# RP2350A_Logic_Analyzer.net
KiCad netlist of a schematic drawn in EAGLE
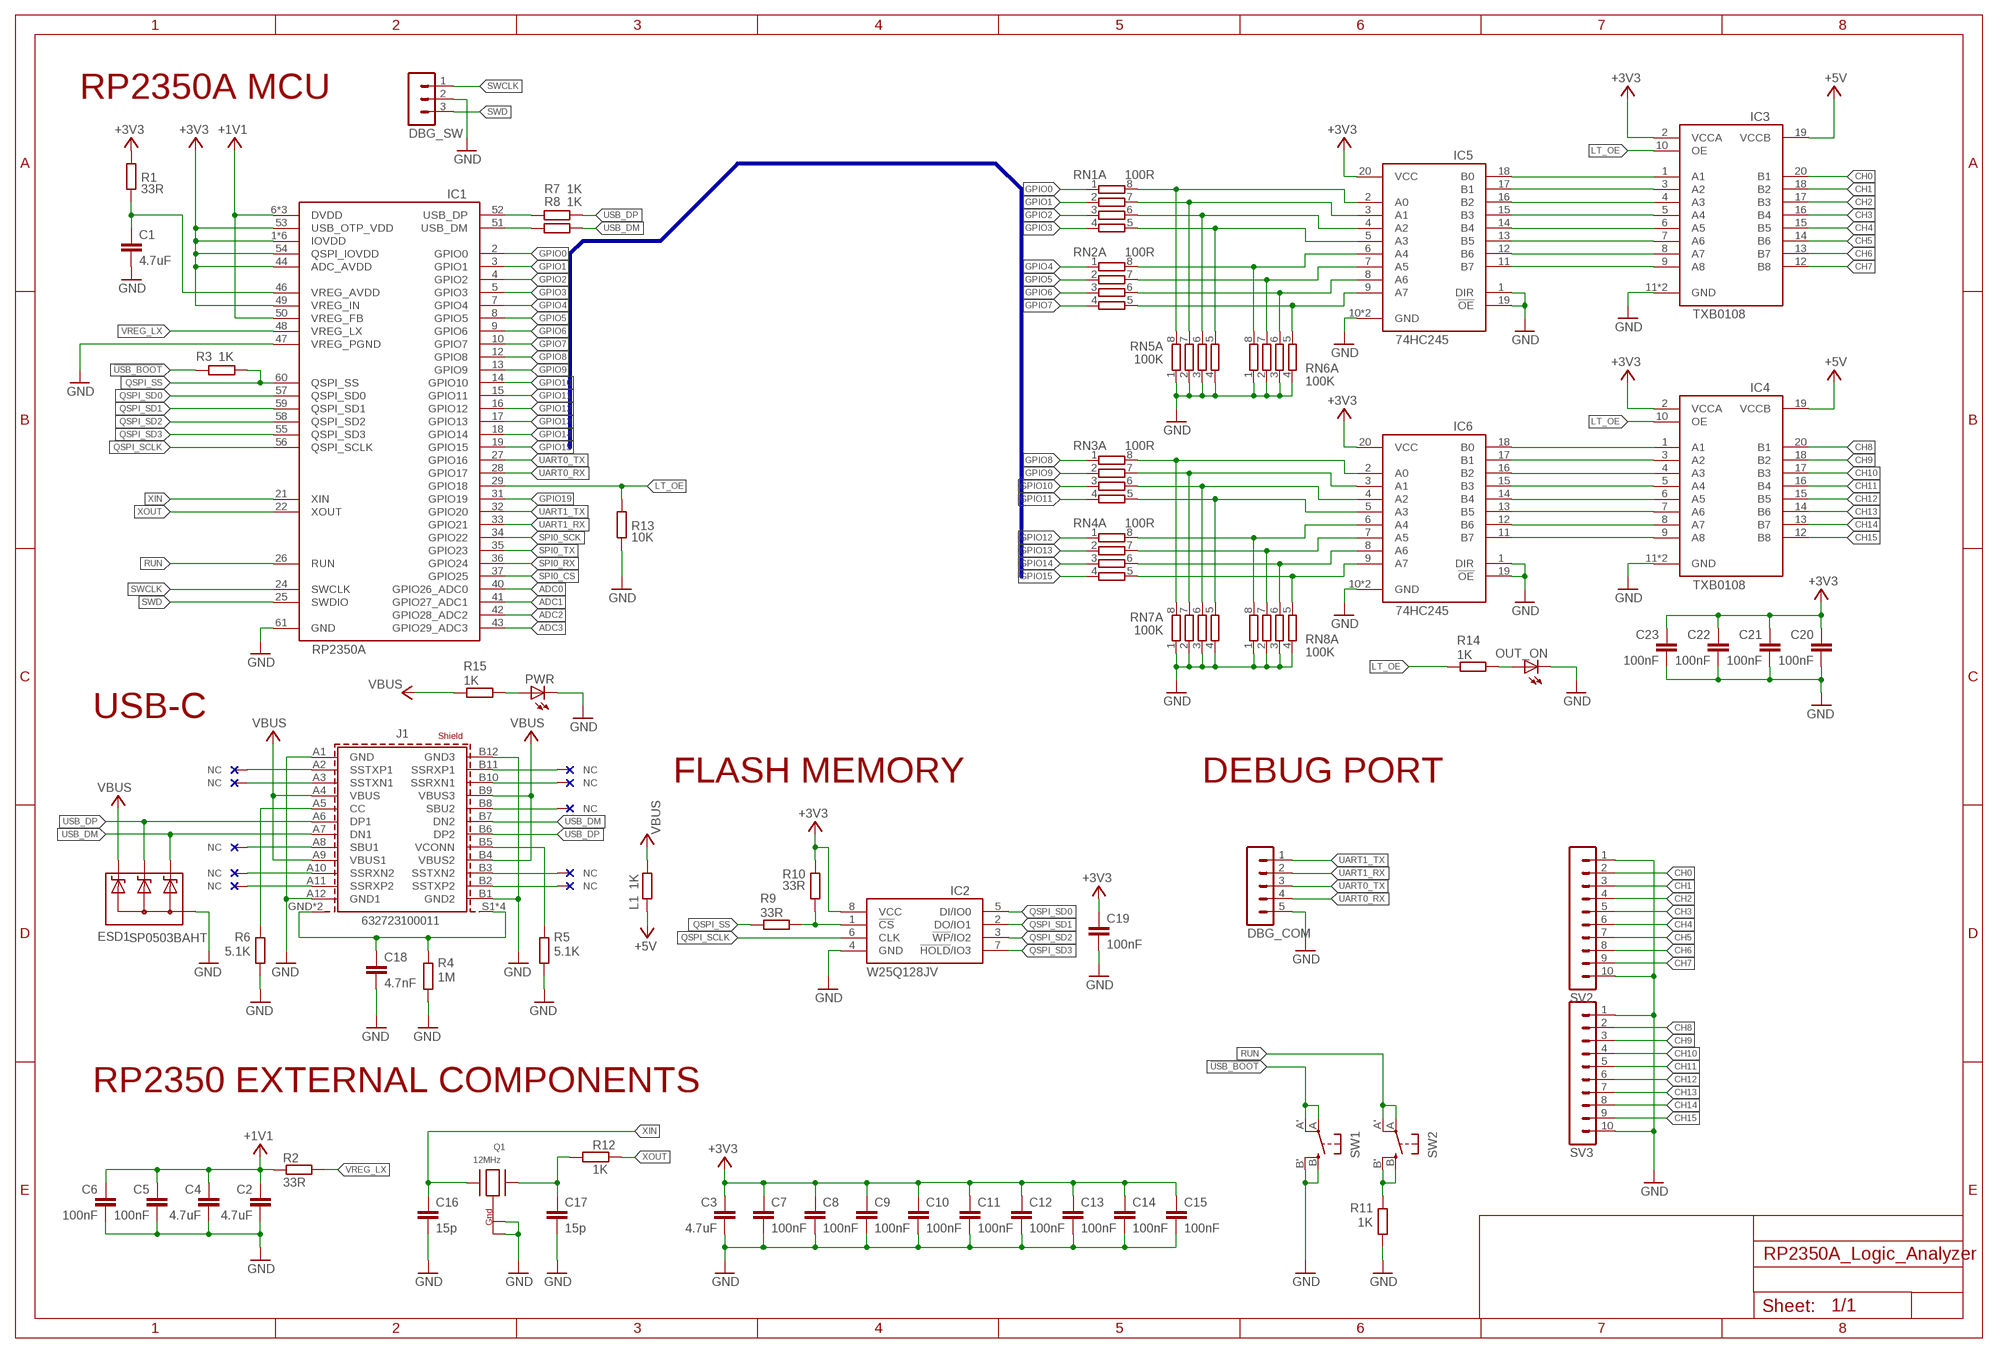
[diagram p0: schematic, sheet 1]

(export (version "E")
  (design (tool "Eeschema 10.0.6"))
  (components
    (comp (ref "C1")
      (value "4.7uF")
      (footprint "eagle-import:C0402")
      (libsource (lib "eagle-import") (part "C-EUC0402"))
    )
    (comp (ref "C2")
      (value "4.7uF")
      (footprint "eagle-import:C0402")
      (libsource (lib "eagle-import") (part "C-EUC0402"))
    )
    (comp (ref "C3")
      (value "4.7uF")
      (footprint "eagle-import:C0402")
      (libsource (lib "eagle-import") (part "C-EUC0402"))
    )
    (comp (ref "C4")
      (value "4.7uF")
      (footprint "eagle-import:C0402")
      (libsource (lib "eagle-import") (part "C-EUC0402"))
    )
    (comp (ref "C5")
      (value "100nF")
      (footprint "eagle-import:C0402")
      (libsource (lib "eagle-import") (part "C-EUC0402"))
    )
    (comp (ref "C6")
      (value "100nF")
      (footprint "eagle-import:C0402")
      (libsource (lib "eagle-import") (part "C-EUC0402"))
    )
    (comp (ref "C7")
      (value "100nF")
      (footprint "eagle-import:C0402")
      (libsource (lib "eagle-import") (part "C-EUC0402"))
    )
    (comp (ref "C8")
      (value "100nF")
      (footprint "eagle-import:C0402")
      (libsource (lib "eagle-import") (part "C-EUC0402"))
    )
    (comp (ref "C9")
      (value "100nF")
      (footprint "eagle-import:C0402")
      (libsource (lib "eagle-import") (part "C-EUC0402"))
    )
    (comp (ref "C10")
      (value "100nF")
      (footprint "eagle-import:C0402")
      (libsource (lib "eagle-import") (part "C-EUC0402"))
    )
    (comp (ref "C11")
      (value "100nF")
      (footprint "eagle-import:C0402")
      (libsource (lib "eagle-import") (part "C-EUC0402"))
    )
    (comp (ref "C12")
      (value "100nF")
      (footprint "eagle-import:C0402")
      (libsource (lib "eagle-import") (part "C-EUC0402"))
    )
    (comp (ref "C13")
      (value "100nF")
      (footprint "eagle-import:C0402")
      (libsource (lib "eagle-import") (part "C-EUC0402"))
    )
    (comp (ref "C14")
      (value "100nF")
      (footprint "eagle-import:C0402")
      (libsource (lib "eagle-import") (part "C-EUC0402"))
    )
    (comp (ref "C15")
      (value "100nF")
      (footprint "eagle-import:C0402")
      (libsource (lib "eagle-import") (part "C-EUC0402"))
    )
    (comp (ref "C16")
      (value "15p")
      (footprint "eagle-import:C0402")
      (libsource (lib "eagle-import") (part "C-EUC0402"))
    )
    (comp (ref "C17")
      (value "15p")
      (footprint "eagle-import:C0402")
      (libsource (lib "eagle-import") (part "C-EUC0402"))
    )
    (comp (ref "C18")
      (value "4.7nF")
      (footprint "eagle-import:C0402")
      (libsource (lib "eagle-import") (part "C-EUC0402"))
    )
    (comp (ref "C19")
      (value "100nF")
      (footprint "eagle-import:C0402")
      (libsource (lib "eagle-import") (part "C-EUC0402"))
    )
    (comp (ref "C20")
      (value "100nF")
      (footprint "eagle-import:C0402")
      (libsource (lib "eagle-import") (part "C-EUC0402"))
    )
    (comp (ref "C21")
      (value "100nF")
      (footprint "eagle-import:C0402")
      (libsource (lib "eagle-import") (part "C-EUC0402"))
    )
    (comp (ref "C22")
      (value "100nF")
      (footprint "eagle-import:C0402")
      (libsource (lib "eagle-import") (part "C-EUC0402"))
    )
    (comp (ref "C23")
      (value "100nF")
      (footprint "eagle-import:C0402")
      (libsource (lib "eagle-import") (part "C-EUC0402"))
    )
    (comp (ref "DBG_COM")
      (value "MA05-1")
      (footprint "eagle-import:MA05-1")
      (libsource (lib "eagle-import") (part "MA05-1"))
    )
    (comp (ref "DBG_SW")
      (value "MA03-1")
      (footprint "eagle-import:MA03-1")
      (libsource (lib "eagle-import") (part "MA03-1"))
    )
    (comp (ref "ESD1")
      (value "SP0503BAHT")
      (footprint "eagle-import:SOT143")
      (libsource (lib "eagle-import") (part "SP0503BAHT"))
    )
    (comp (ref "IC1")
      (value "RP2350AA")
      (footprint "eagle-import:QFN40P700X700X85-61T340N")
      (libsource (lib "eagle-import") (part "RP2350AA"))
    )
    (comp (ref "IC2")
      (value "W25Q128JVP")
      (footprint "eagle-import:SON127P600X500X75-8N")
      (libsource (lib "eagle-import") (part "W25Q128JVP"))
    )
    (comp (ref "IC3")
      (value "TXB0108RGY")
      (footprint "eagle-import:QFN50P350X450X100-25T200X300N")
      (libsource (lib "eagle-import") (part "TXB0108RGY"))
    )
    (comp (ref "IC4")
      (value "TXB0108RGY")
      (footprint "eagle-import:QFN50P350X450X100-25T200X300N")
      (libsource (lib "eagle-import") (part "TXB0108RGY"))
    )
    (comp (ref "IC5")
      (value "74HC245BQ")
      (footprint "eagle-import:QFN50P250X450X90-21T100X300N")
      (libsource (lib "eagle-import") (part "74HC245BQ"))
    )
    (comp (ref "IC6")
      (value "74HC245BQ")
      (footprint "eagle-import:QFN50P250X450X90-21T100X300N")
      (libsource (lib "eagle-import") (part "74HC245BQ"))
    )
    (comp (ref "J1")
      (value "632723100011")
      (footprint "eagle-import:632723100011")
      (libsource (lib "eagle-import") (part "632723100011"))
    )
    (comp (ref "L1")
      (value "1K")
      (footprint "eagle-import:R0402")
      (libsource (lib "eagle-import") (part "R-EU_R0402"))
    )
    (comp (ref "OUT_ON")
      (value "LEDCHIPLED_0603")
      (footprint "eagle-import:CHIPLED_0603")
      (libsource (lib "eagle-import") (part "LEDCHIPLED_0603"))
    )
    (comp (ref "PWR")
      (value "LEDCHIPLED_0603")
      (footprint "eagle-import:CHIPLED_0603")
      (libsource (lib "eagle-import") (part "LEDCHIPLED_0603"))
    )
    (comp (ref "Q1")
      (value "12MHz")
      (footprint "eagle-import:NX3225")
      (libsource (lib "eagle-import") (part "XTAL-4-3225"))
    )
    (comp (ref "R1")
      (value "33R")
      (footprint "eagle-import:R0402")
      (libsource (lib "eagle-import") (part "R-EU_R0402"))
    )
    (comp (ref "R2")
      (value "33R")
      (footprint "eagle-import:R0402")
      (libsource (lib "eagle-import") (part "R-EU_R0402"))
    )
    (comp (ref "R3")
      (value "1K")
      (footprint "eagle-import:R0402")
      (libsource (lib "eagle-import") (part "R-EU_R0402"))
    )
    (comp (ref "R4")
      (value "1M")
      (footprint "eagle-import:R0402")
      (libsource (lib "eagle-import") (part "R-EU_R0402"))
    )
    (comp (ref "R5")
      (value "5.1K")
      (footprint "eagle-import:R0402")
      (libsource (lib "eagle-import") (part "R-EU_R0402"))
    )
    (comp (ref "R6")
      (value "5.1K")
      (footprint "eagle-import:R0402")
      (libsource (lib "eagle-import") (part "R-EU_R0402"))
    )
    (comp (ref "R7")
      (value "1K")
      (footprint "eagle-import:R0402")
      (libsource (lib "eagle-import") (part "R-EU_R0402"))
    )
    (comp (ref "R8")
      (value "1K")
      (footprint "eagle-import:R0402")
      (libsource (lib "eagle-import") (part "R-EU_R0402"))
    )
    (comp (ref "R9")
      (value "33R")
      (footprint "eagle-import:R0402")
      (libsource (lib "eagle-import") (part "R-EU_R0402"))
    )
    (comp (ref "R10")
      (value "33R")
      (footprint "eagle-import:R0402")
      (libsource (lib "eagle-import") (part "R-EU_R0402"))
    )
    (comp (ref "R11")
      (value "1K")
      (footprint "eagle-import:R0402")
      (libsource (lib "eagle-import") (part "R-EU_R0402"))
    )
    (comp (ref "R12")
      (value "1K")
      (footprint "eagle-import:R0402")
      (libsource (lib "eagle-import") (part "R-EU_R0402"))
    )
    (comp (ref "R13")
      (value "10K")
      (footprint "eagle-import:R0402")
      (libsource (lib "eagle-import") (part "R-EU_R0402"))
    )
    (comp (ref "R14")
      (value "1K")
      (footprint "eagle-import:R0402")
      (libsource (lib "eagle-import") (part "R-EU_R0402"))
    )
    (comp (ref "R15")
      (value "1K")
      (footprint "eagle-import:R0402")
      (libsource (lib "eagle-import") (part "R-EU_R0402"))
    )
    (comp (ref "RN1")
      (value "100R")
      (footprint "eagle-import:0603-ARC")
      (libsource (lib "eagle-import") (part "4R-N0603-ARC"))
    )
    (comp (ref "RN2")
      (value "100R")
      (footprint "eagle-import:0603-ARC")
      (libsource (lib "eagle-import") (part "4R-N0603-ARC"))
    )
    (comp (ref "RN3")
      (value "100R")
      (footprint "eagle-import:0603-ARC")
      (libsource (lib "eagle-import") (part "4R-N0603-ARC"))
    )
    (comp (ref "RN4")
      (value "100R")
      (footprint "eagle-import:0603-ARC")
      (libsource (lib "eagle-import") (part "4R-N0603-ARC"))
    )
    (comp (ref "RN5")
      (value "100K")
      (footprint "eagle-import:0603-ARC")
      (libsource (lib "eagle-import") (part "4R-N0603-ARC"))
    )
    (comp (ref "RN6")
      (value "100K")
      (footprint "eagle-import:0603-ARC")
      (libsource (lib "eagle-import") (part "4R-N0603-ARC"))
    )
    (comp (ref "RN7")
      (value "100K")
      (footprint "eagle-import:0603-ARC")
      (libsource (lib "eagle-import") (part "4R-N0603-ARC"))
    )
    (comp (ref "RN8")
      (value "100K")
      (footprint "eagle-import:0603-ARC")
      (libsource (lib "eagle-import") (part "4R-N0603-ARC"))
    )
    (comp (ref "SV2")
      (value "MA10-1")
      (footprint "eagle-import:MA10-1")
      (libsource (lib "eagle-import") (part "MA10-1"))
    )
    (comp (ref "SV3")
      (value "MA10-1")
      (footprint "eagle-import:MA10-1")
      (libsource (lib "eagle-import") (part "MA10-1"))
    )
    (comp (ref "SW1")
      (value "SPST_TACT-EVQQ2")
      (footprint "eagle-import:EVQ-Q2")
      (libsource (lib "eagle-import") (part "SPST_TACT-EVQQ2"))
    )
    (comp (ref "SW2")
      (value "SPST_TACT-EVQQ2")
      (footprint "eagle-import:EVQ-Q2")
      (libsource (lib "eagle-import") (part "SPST_TACT-EVQQ2"))
    )
  )
  (nets
    (net (code "1") (name "+1V1") (class "Default")
      (node (ref "C2") (pin "1") (pinfunction "1_1") (pintype "passive"))
      (node (ref "C4") (pin "1") (pinfunction "1_1") (pintype "passive"))
      (node (ref "C5") (pin "1") (pinfunction "1_1") (pintype "passive"))
      (node (ref "C6") (pin "1") (pinfunction "1_1") (pintype "passive"))
      (node (ref "IC1") (pin "23") (pinfunction "DVDD_23") (pintype "power_in"))
      (node (ref "IC1") (pin "39") (pinfunction "DVDD_39") (pintype "power_in"))
      (node (ref "IC1") (pin "50") (pinfunction "VREG_FB_50") (pintype "power_in"))
      (node (ref "IC1") (pin "6") (pinfunction "DVDD_6") (pintype "power_in"))
      (node (ref "R2") (pin "2") (pinfunction "2_2") (pintype "passive"))
    )
    (net (code "2") (name "+3V3") (class "Default")
      (node (ref "C10") (pin "1") (pinfunction "1_1") (pintype "passive"))
      (node (ref "C11") (pin "1") (pinfunction "1_1") (pintype "passive"))
      (node (ref "C12") (pin "1") (pinfunction "1_1") (pintype "passive"))
      (node (ref "C13") (pin "1") (pinfunction "1_1") (pintype "passive"))
      (node (ref "C14") (pin "1") (pinfunction "1_1") (pintype "passive"))
      (node (ref "C15") (pin "1") (pinfunction "1_1") (pintype "passive"))
      (node (ref "C19") (pin "1") (pinfunction "1_1") (pintype "passive"))
      (node (ref "C20") (pin "1") (pinfunction "1_1") (pintype "passive"))
      (node (ref "C21") (pin "1") (pinfunction "1_1") (pintype "passive"))
      (node (ref "C22") (pin "1") (pinfunction "1_1") (pintype "passive"))
      (node (ref "C23") (pin "1") (pinfunction "1_1") (pintype "passive"))
      (node (ref "C3") (pin "1") (pinfunction "1_1") (pintype "passive"))
      (node (ref "C7") (pin "1") (pinfunction "1_1") (pintype "passive"))
      (node (ref "C8") (pin "1") (pinfunction "1_1") (pintype "passive"))
      (node (ref "C9") (pin "1") (pinfunction "1_1") (pintype "passive"))
      (node (ref "IC1") (pin "1") (pinfunction "IOVDD_1") (pintype "power_in"))
      (node (ref "IC1") (pin "11") (pinfunction "IOVDD_11") (pintype "power_in"))
      (node (ref "IC1") (pin "20") (pinfunction "IOVDD_20") (pintype "power_in"))
      (node (ref "IC1") (pin "30") (pinfunction "IOVDD_30") (pintype "power_in"))
      (node (ref "IC1") (pin "38") (pinfunction "IOVDD_38") (pintype "power_in"))
      (node (ref "IC1") (pin "44") (pinfunction "ADC_AVDD_44") (pintype "power_in"))
      (node (ref "IC1") (pin "45") (pinfunction "IOVDD_45") (pintype "power_in"))
      (node (ref "IC1") (pin "49") (pinfunction "VREG_IN_49") (pintype "power_in"))
      (node (ref "IC1") (pin "53") (pinfunction "USB_OTP_VDD_53") (pintype "bidirectional"))
      (node (ref "IC1") (pin "54") (pinfunction "QSPI_IOVDD_54") (pintype "power_in"))
      (node (ref "IC2") (pin "8") (pinfunction "VCC_8") (pintype "power_in"))
      (node (ref "IC3") (pin "2") (pinfunction "VCCA_2") (pintype "power_in"))
      (node (ref "IC4") (pin "2") (pinfunction "VCCA_2") (pintype "power_in"))
      (node (ref "IC5") (pin "20") (pinfunction "VCC_20") (pintype "power_in"))
      (node (ref "IC6") (pin "20") (pinfunction "VCC_20") (pintype "power_in"))
      (node (ref "R1") (pin "1") (pinfunction "1_1") (pintype "passive"))
      (node (ref "R10") (pin "1") (pinfunction "1_1") (pintype "passive"))
    )
    (net (code "3") (name "+5V") (class "Default")
      (node (ref "IC3") (pin "19") (pinfunction "VCCB_19") (pintype "power_in"))
      (node (ref "IC4") (pin "19") (pinfunction "VCCB_19") (pintype "power_in"))
      (node (ref "L1") (pin "1") (pinfunction "1_1") (pintype "passive"))
    )
    (net (code "4") (name "/~{USB_BOOT}") (class "Default")
      (node (ref "R3") (pin "1") (pinfunction "1_1") (pintype "passive"))
      (node (ref "SW1") (pin "A") (pinfunction "P_A") (pintype "passive"))
      (node (ref "SW1") (pin "A'") (pinfunction "P1_A'") (pintype "passive"))
    )
    (net (code "5") (name "ADC0") (class "Default")
      (node (ref "IC1") (pin "40") (pinfunction "GPIO26_ADC0_40") (pintype "bidirectional"))
    )
    (net (code "6") (name "ADC1") (class "Default")
      (node (ref "IC1") (pin "41") (pinfunction "GPIO27_ADC1_41") (pintype "bidirectional"))
    )
    (net (code "7") (name "ADC2") (class "Default")
      (node (ref "IC1") (pin "42") (pinfunction "GPIO28_ADC2_42") (pintype "bidirectional"))
    )
    (net (code "8") (name "ADC3") (class "Default")
      (node (ref "IC1") (pin "43") (pinfunction "GPIO29_ADC3_43") (pintype "bidirectional"))
    )
    (net (code "9") (name "CH0") (class "Default")
      (node (ref "IC3") (pin "20") (pinfunction "B1_20") (pintype "bidirectional"))
      (node (ref "SV2") (pin "2") (pinfunction "2_2") (pintype "passive"))
    )
    (net (code "10") (name "CH1") (class "Default")
      (node (ref "IC3") (pin "18") (pinfunction "B2_18") (pintype "bidirectional"))
      (node (ref "SV2") (pin "3") (pinfunction "3_3") (pintype "passive"))
    )
    (net (code "11") (name "CH2") (class "Default")
      (node (ref "IC3") (pin "17") (pinfunction "B3_17") (pintype "bidirectional"))
      (node (ref "SV2") (pin "4") (pinfunction "4_4") (pintype "passive"))
    )
    (net (code "12") (name "CH3") (class "Default")
      (node (ref "IC3") (pin "16") (pinfunction "B4_16") (pintype "bidirectional"))
      (node (ref "SV2") (pin "5") (pinfunction "5_5") (pintype "passive"))
    )
    (net (code "13") (name "CH4") (class "Default")
      (node (ref "IC3") (pin "15") (pinfunction "B5_15") (pintype "bidirectional"))
      (node (ref "SV2") (pin "6") (pinfunction "6_6") (pintype "passive"))
    )
    (net (code "14") (name "CH5") (class "Default")
      (node (ref "IC3") (pin "14") (pinfunction "B6_14") (pintype "bidirectional"))
      (node (ref "SV2") (pin "7") (pinfunction "7_7") (pintype "passive"))
    )
    (net (code "15") (name "CH6") (class "Default")
      (node (ref "IC3") (pin "13") (pinfunction "B7_13") (pintype "bidirectional"))
      (node (ref "SV2") (pin "8") (pinfunction "8_8") (pintype "passive"))
    )
    (net (code "16") (name "CH7") (class "Default")
      (node (ref "IC3") (pin "12") (pinfunction "B8_12") (pintype "bidirectional"))
      (node (ref "SV2") (pin "9") (pinfunction "9_9") (pintype "passive"))
    )
    (net (code "17") (name "CH8") (class "Default")
      (node (ref "IC4") (pin "20") (pinfunction "B1_20") (pintype "bidirectional"))
      (node (ref "SV3") (pin "2") (pinfunction "2_2") (pintype "passive"))
    )
    (net (code "18") (name "CH9") (class "Default")
      (node (ref "IC4") (pin "18") (pinfunction "B2_18") (pintype "bidirectional"))
      (node (ref "SV3") (pin "3") (pinfunction "3_3") (pintype "passive"))
    )
    (net (code "19") (name "CH10") (class "Default")
      (node (ref "IC4") (pin "17") (pinfunction "B3_17") (pintype "bidirectional"))
      (node (ref "SV3") (pin "4") (pinfunction "4_4") (pintype "passive"))
    )
    (net (code "20") (name "CH11") (class "Default")
      (node (ref "IC4") (pin "16") (pinfunction "B4_16") (pintype "bidirectional"))
      (node (ref "SV3") (pin "5") (pinfunction "5_5") (pintype "passive"))
    )
    (net (code "21") (name "CH12") (class "Default")
      (node (ref "IC4") (pin "15") (pinfunction "B5_15") (pintype "bidirectional"))
      (node (ref "SV3") (pin "6") (pinfunction "6_6") (pintype "passive"))
    )
    (net (code "22") (name "CH13") (class "Default")
      (node (ref "IC4") (pin "14") (pinfunction "B6_14") (pintype "bidirectional"))
      (node (ref "SV3") (pin "7") (pinfunction "7_7") (pintype "passive"))
    )
    (net (code "23") (name "CH14") (class "Default")
      (node (ref "IC4") (pin "13") (pinfunction "B7_13") (pintype "bidirectional"))
      (node (ref "SV3") (pin "8") (pinfunction "8_8") (pintype "passive"))
    )
    (net (code "24") (name "CH15") (class "Default")
      (node (ref "IC4") (pin "12") (pinfunction "B8_12") (pintype "bidirectional"))
      (node (ref "SV3") (pin "9") (pinfunction "9_9") (pintype "passive"))
    )
    (net (code "25") (name "GND") (class "Default")
      (node (ref "C1") (pin "2") (pinfunction "2_2") (pintype "passive"))
      (node (ref "C10") (pin "2") (pinfunction "2_2") (pintype "passive"))
      (node (ref "C11") (pin "2") (pinfunction "2_2") (pintype "passive"))
      (node (ref "C12") (pin "2") (pinfunction "2_2") (pintype "passive"))
      (node (ref "C13") (pin "2") (pinfunction "2_2") (pintype "passive"))
      (node (ref "C14") (pin "2") (pinfunction "2_2") (pintype "passive"))
      (node (ref "C15") (pin "2") (pinfunction "2_2") (pintype "passive"))
      (node (ref "C16") (pin "2") (pinfunction "2_2") (pintype "passive"))
      (node (ref "C17") (pin "2") (pinfunction "2_2") (pintype "passive"))
      (node (ref "C18") (pin "2") (pinfunction "2_2") (pintype "passive"))
      (node (ref "C19") (pin "2") (pinfunction "2_2") (pintype "passive"))
      (node (ref "C2") (pin "2") (pinfunction "2_2") (pintype "passive"))
      (node (ref "C20") (pin "2") (pinfunction "2_2") (pintype "passive"))
      (node (ref "C21") (pin "2") (pinfunction "2_2") (pintype "passive"))
      (node (ref "C22") (pin "2") (pinfunction "2_2") (pintype "passive"))
      (node (ref "C23") (pin "2") (pinfunction "2_2") (pintype "passive"))
      (node (ref "C3") (pin "2") (pinfunction "2_2") (pintype "passive"))
      (node (ref "C4") (pin "2") (pinfunction "2_2") (pintype "passive"))
      (node (ref "C5") (pin "2") (pinfunction "2_2") (pintype "passive"))
      (node (ref "C6") (pin "2") (pinfunction "2_2") (pintype "passive"))
      (node (ref "C7") (pin "2") (pinfunction "2_2") (pintype "passive"))
      (node (ref "C8") (pin "2") (pinfunction "2_2") (pintype "passive"))
      (node (ref "C9") (pin "2") (pinfunction "2_2") (pintype "passive"))
      (node (ref "DBG_COM") (pin "5") (pinfunction "5_5") (pintype "passive"))
      (node (ref "DBG_SW") (pin "2") (pinfunction "2_2") (pintype "passive"))
      (node (ref "ESD1") (pin "1") (pinfunction "A_1") (pintype "bidirectional"))
      (node (ref "IC1") (pin "47") (pinfunction "VREG_PGND_47") (pintype "power_in"))
      (node (ref "IC1") (pin "61") (pinfunction "GND_61") (pintype "power_in"))
      (node (ref "IC2") (pin "4") (pinfunction "GND_4") (pintype "power_in"))
      (node (ref "IC3") (pin "11") (pinfunction "GND_11") (pintype "power_in"))
      (node (ref "IC3") (pin "PAD") (pinfunction "GND_PAD") (pintype "power_in"))
      (node (ref "IC4") (pin "11") (pinfunction "GND_11") (pintype "power_in"))
      (node (ref "IC4") (pin "PAD") (pinfunction "GND_PAD") (pintype "power_in"))
      (node (ref "IC5") (pin "1") (pinfunction "DIR_1") (pintype "input"))
      (node (ref "IC5") (pin "10") (pinfunction "GND_10") (pintype "power_in"))
      (node (ref "IC5") (pin "19") (pinfunction "~{OE}_19") (pintype "input"))
      (node (ref "IC5") (pin "PAD") (pinfunction "GND_PAD") (pintype "power_in"))
      (node (ref "IC6") (pin "1") (pinfunction "DIR_1") (pintype "input"))
      (node (ref "IC6") (pin "10") (pinfunction "GND_10") (pintype "power_in"))
      (node (ref "IC6") (pin "19") (pinfunction "~{OE}_19") (pintype "input"))
      (node (ref "IC6") (pin "PAD") (pinfunction "GND_PAD") (pintype "power_in"))
      (node (ref "J1") (pin "A1") (pinfunction "GND_A1") (pintype "passive"))
      (node (ref "J1") (pin "A12") (pinfunction "GND1_A12") (pintype "passive"))
      (node (ref "J1") (pin "B1") (pinfunction "GND2_B1") (pintype "passive"))
      (node (ref "J1") (pin "B12") (pinfunction "GND3_B12") (pintype "passive"))
      (node (ref "OUT_ON") (pin "C") (pinfunction "C_C") (pintype "passive"))
      (node (ref "PWR") (pin "C") (pinfunction "C_C") (pintype "passive"))
      (node (ref "Q1") (pin "2") (pinfunction "G2_2") (pintype "power_in"))
      (node (ref "Q1") (pin "4") (pinfunction "G1_4") (pintype "power_in"))
      (node (ref "R11") (pin "1") (pinfunction "1_1") (pintype "passive"))
      (node (ref "R13") (pin "2") (pinfunction "2_2") (pintype "passive"))
      (node (ref "R4") (pin "1") (pinfunction "1_1") (pintype "passive"))
      (node (ref "R5") (pin "1") (pinfunction "1_1") (pintype "passive"))
      (node (ref "R6") (pin "1") (pinfunction "1_1") (pintype "passive"))
      (node (ref "RN5") (pin "1") (pinfunction "1_1") (pintype "passive"))
      (node (ref "RN5") (pin "2") (pinfunction "1_2") (pintype "passive"))
      (node (ref "RN5") (pin "3") (pinfunction "1_3") (pintype "passive"))
      (node (ref "RN5") (pin "4") (pinfunction "1_4") (pintype "passive"))
      (node (ref "RN6") (pin "1") (pinfunction "1_1") (pintype "passive"))
      (node (ref "RN6") (pin "2") (pinfunction "1_2") (pintype "passive"))
      (node (ref "RN6") (pin "3") (pinfunction "1_3") (pintype "passive"))
      (node (ref "RN6") (pin "4") (pinfunction "1_4") (pintype "passive"))
      (node (ref "RN7") (pin "1") (pinfunction "1_1") (pintype "passive"))
      (node (ref "RN7") (pin "2") (pinfunction "1_2") (pintype "passive"))
      (node (ref "RN7") (pin "3") (pinfunction "1_3") (pintype "passive"))
      (node (ref "RN7") (pin "4") (pinfunction "1_4") (pintype "passive"))
      (node (ref "RN8") (pin "1") (pinfunction "1_1") (pintype "passive"))
      (node (ref "RN8") (pin "2") (pinfunction "1_2") (pintype "passive"))
      (node (ref "RN8") (pin "3") (pinfunction "1_3") (pintype "passive"))
      (node (ref "RN8") (pin "4") (pinfunction "1_4") (pintype "passive"))
      (node (ref "SV2") (pin "1") (pinfunction "1_1") (pintype "passive"))
      (node (ref "SV2") (pin "10") (pinfunction "10_10") (pintype "passive"))
      (node (ref "SV3") (pin "1") (pinfunction "1_1") (pintype "passive"))
      (node (ref "SV3") (pin "10") (pinfunction "10_10") (pintype "passive"))
      (node (ref "SW1") (pin "B") (pinfunction "S_B") (pintype "passive"))
      (node (ref "SW1") (pin "B'") (pinfunction "S1_B'") (pintype "passive"))
    )
    (net (code "26") (name "GPIO0") (class "Default")
      (node (ref "IC1") (pin "2") (pinfunction "GPIO0_2") (pintype "bidirectional"))
      (node (ref "RN1") (pin "1") (pinfunction "1_1") (pintype "passive"))
    )
    (net (code "27") (name "GPIO1") (class "Default")
      (node (ref "IC1") (pin "3") (pinfunction "GPIO1_3") (pintype "bidirectional"))
      (node (ref "RN1") (pin "2") (pinfunction "1_2") (pintype "passive"))
    )
    (net (code "28") (name "GPIO2") (class "Default")
      (node (ref "IC1") (pin "4") (pinfunction "GPIO2_4") (pintype "bidirectional"))
      (node (ref "RN1") (pin "3") (pinfunction "1_3") (pintype "passive"))
    )
    (net (code "29") (name "GPIO3") (class "Default")
      (node (ref "IC1") (pin "5") (pinfunction "GPIO3_5") (pintype "bidirectional"))
      (node (ref "RN1") (pin "4") (pinfunction "1_4") (pintype "passive"))
    )
    (net (code "30") (name "GPIO4") (class "Default")
      (node (ref "IC1") (pin "7") (pinfunction "GPIO4_7") (pintype "bidirectional"))
      (node (ref "RN2") (pin "1") (pinfunction "1_1") (pintype "passive"))
    )
    (net (code "31") (name "GPIO5") (class "Default")
      (node (ref "IC1") (pin "8") (pinfunction "GPIO5_8") (pintype "bidirectional"))
      (node (ref "RN2") (pin "2") (pinfunction "1_2") (pintype "passive"))
    )
    (net (code "32") (name "GPIO6") (class "Default")
      (node (ref "IC1") (pin "9") (pinfunction "GPIO6_9") (pintype "bidirectional"))
      (node (ref "RN2") (pin "3") (pinfunction "1_3") (pintype "passive"))
    )
    (net (code "33") (name "GPIO7") (class "Default")
      (node (ref "IC1") (pin "10") (pinfunction "GPIO7_10") (pintype "bidirectional"))
      (node (ref "RN2") (pin "4") (pinfunction "1_4") (pintype "passive"))
    )
    (net (code "34") (name "GPIO8") (class "Default")
      (node (ref "IC1") (pin "12") (pinfunction "GPIO8_12") (pintype "bidirectional"))
      (node (ref "RN3") (pin "1") (pinfunction "1_1") (pintype "passive"))
    )
    (net (code "35") (name "GPIO9") (class "Default")
      (node (ref "IC1") (pin "13") (pinfunction "GPIO9_13") (pintype "bidirectional"))
      (node (ref "RN3") (pin "2") (pinfunction "1_2") (pintype "passive"))
    )
    (net (code "36") (name "GPIO10") (class "Default")
      (node (ref "IC1") (pin "14") (pinfunction "GPIO10_14") (pintype "bidirectional"))
      (node (ref "RN3") (pin "3") (pinfunction "1_3") (pintype "passive"))
    )
    (net (code "37") (name "GPIO11") (class "Default")
      (node (ref "IC1") (pin "15") (pinfunction "GPIO11_15") (pintype "bidirectional"))
      (node (ref "RN3") (pin "4") (pinfunction "1_4") (pintype "passive"))
    )
    (net (code "38") (name "GPIO12") (class "Default")
      (node (ref "IC1") (pin "16") (pinfunction "GPIO12_16") (pintype "bidirectional"))
      (node (ref "RN4") (pin "1") (pinfunction "1_1") (pintype "passive"))
    )
    (net (code "39") (name "GPIO13") (class "Default")
      (node (ref "IC1") (pin "17") (pinfunction "GPIO13_17") (pintype "bidirectional"))
      (node (ref "RN4") (pin "2") (pinfunction "1_2") (pintype "passive"))
    )
    (net (code "40") (name "GPIO14") (class "Default")
      (node (ref "IC1") (pin "18") (pinfunction "GPIO14_18") (pintype "bidirectional"))
      (node (ref "RN4") (pin "3") (pinfunction "1_3") (pintype "passive"))
    )
    (net (code "41") (name "GPIO15") (class "Default")
      (node (ref "IC1") (pin "19") (pinfunction "GPIO15_19") (pintype "bidirectional"))
      (node (ref "RN4") (pin "4") (pinfunction "1_4") (pintype "passive"))
    )
    (net (code "42") (name "GPIO19") (class "Default")
      (node (ref "IC1") (pin "31") (pinfunction "GPIO19_31") (pintype "bidirectional"))
    )
    (net (code "43") (name "LT_OE") (class "Default")
      (node (ref "IC1") (pin "29") (pinfunction "GPIO18_29") (pintype "bidirectional"))
      (node (ref "IC3") (pin "10") (pinfunction "OE_10") (pintype "input"))
      (node (ref "IC4") (pin "10") (pinfunction "OE_10") (pintype "input"))
      (node (ref "R13") (pin "1") (pinfunction "1_1") (pintype "passive"))
      (node (ref "R14") (pin "1") (pinfunction "1_1") (pintype "passive"))
    )
    (net (code "44") (name "Net-(C18-Pad1)") (class "Default")
      (node (ref "C18") (pin "1") (pinfunction "1_1") (pintype "passive"))
      (node (ref "J1") (pin "GND") (pinfunction "SHIELD_GND") (pintype "passive"))
      (node (ref "J1") (pin "GND1") (pinfunction "SHIELD_GND1") (pintype "passive"))
      (node (ref "J1") (pin "S1") (pinfunction "SHIELD1_S1") (pintype "passive"))
      (node (ref "J1") (pin "S2") (pinfunction "SHIELD1_S2") (pintype "passive"))
      (node (ref "J1") (pin "S3") (pinfunction "SHIELD1_S3") (pintype "passive"))
      (node (ref "J1") (pin "S4") (pinfunction "SHIELD1_S4") (pintype "passive"))
      (node (ref "R4") (pin "2") (pinfunction "2_2") (pintype "passive"))
    )
    (net (code "45") (name "Net-(IC1-USB_DM)") (class "Default")
      (node (ref "IC1") (pin "51") (pinfunction "USB_DM_51") (pintype "bidirectional"))
      (node (ref "R8") (pin "1") (pinfunction "1_1") (pintype "passive"))
    )
    (net (code "46") (name "Net-(IC1-USB_DP)") (class "Default")
      (node (ref "IC1") (pin "52") (pinfunction "USB_DP_52") (pintype "bidirectional"))
      (node (ref "R7") (pin "1") (pinfunction "1_1") (pintype "passive"))
    )
    (net (code "47") (name "Net-(IC1-VREG_AVDD)") (class "Default")
      (node (ref "C1") (pin "1") (pinfunction "1_1") (pintype "passive"))
      (node (ref "IC1") (pin "46") (pinfunction "VREG_AVDD_46") (pintype "power_in"))
      (node (ref "R1") (pin "2") (pinfunction "2_2") (pintype "passive"))
    )
    (net (code "48") (name "Net-(IC2-~{CS})") (class "Default")
      (node (ref "IC2") (pin "1") (pinfunction "~{CS}_1") (pintype "bidirectional"))
      (node (ref "R10") (pin "2") (pinfunction "2_2") (pintype "passive"))
      (node (ref "R9") (pin "2") (pinfunction "2_2") (pintype "passive"))
    )
    (net (code "49") (name "Net-(IC3-A1)") (class "Default")
      (node (ref "IC3") (pin "1") (pinfunction "A1_1") (pintype "bidirectional"))
      (node (ref "IC5") (pin "18") (pinfunction "B0_18") (pintype "bidirectional"))
    )
    (net (code "50") (name "Net-(IC3-A2)") (class "Default")
      (node (ref "IC3") (pin "3") (pinfunction "A2_3") (pintype "bidirectional"))
      (node (ref "IC5") (pin "17") (pinfunction "B1_17") (pintype "bidirectional"))
    )
    (net (code "51") (name "Net-(IC3-A3)") (class "Default")
      (node (ref "IC3") (pin "4") (pinfunction "A3_4") (pintype "bidirectional"))
      (node (ref "IC5") (pin "16") (pinfunction "B2_16") (pintype "bidirectional"))
    )
    (net (code "52") (name "Net-(IC3-A4)") (class "Default")
      (node (ref "IC3") (pin "5") (pinfunction "A4_5") (pintype "bidirectional"))
      (node (ref "IC5") (pin "15") (pinfunction "B3_15") (pintype "bidirectional"))
    )
    (net (code "53") (name "Net-(IC3-A5)") (class "Default")
      (node (ref "IC3") (pin "6") (pinfunction "A5_6") (pintype "bidirectional"))
      (node (ref "IC5") (pin "14") (pinfunction "B4_14") (pintype "bidirectional"))
    )
    (net (code "54") (name "Net-(IC3-A6)") (class "Default")
      (node (ref "IC3") (pin "7") (pinfunction "A6_7") (pintype "bidirectional"))
      (node (ref "IC5") (pin "13") (pinfunction "B5_13") (pintype "bidirectional"))
    )
    (net (code "55") (name "Net-(IC3-A7)") (class "Default")
      (node (ref "IC3") (pin "8") (pinfunction "A7_8") (pintype "bidirectional"))
      (node (ref "IC5") (pin "12") (pinfunction "B6_12") (pintype "bidirectional"))
    )
    (net (code "56") (name "Net-(IC3-A8)") (class "Default")
      (node (ref "IC3") (pin "9") (pinfunction "A8_9") (pintype "bidirectional"))
      (node (ref "IC5") (pin "11") (pinfunction "B7_11") (pintype "bidirectional"))
    )
    (net (code "57") (name "Net-(IC4-A1)") (class "Default")
      (node (ref "IC4") (pin "1") (pinfunction "A1_1") (pintype "bidirectional"))
      (node (ref "IC6") (pin "18") (pinfunction "B0_18") (pintype "bidirectional"))
    )
    (net (code "58") (name "Net-(IC4-A2)") (class "Default")
      (node (ref "IC4") (pin "3") (pinfunction "A2_3") (pintype "bidirectional"))
      (node (ref "IC6") (pin "17") (pinfunction "B1_17") (pintype "bidirectional"))
    )
    (net (code "59") (name "Net-(IC4-A3)") (class "Default")
      (node (ref "IC4") (pin "4") (pinfunction "A3_4") (pintype "bidirectional"))
      (node (ref "IC6") (pin "16") (pinfunction "B2_16") (pintype "bidirectional"))
    )
    (net (code "60") (name "Net-(IC4-A4)") (class "Default")
      (node (ref "IC4") (pin "5") (pinfunction "A4_5") (pintype "bidirectional"))
      (node (ref "IC6") (pin "15") (pinfunction "B3_15") (pintype "bidirectional"))
    )
    (net (code "61") (name "Net-(IC4-A5)") (class "Default")
      (node (ref "IC4") (pin "6") (pinfunction "A5_6") (pintype "bidirectional"))
      (node (ref "IC6") (pin "14") (pinfunction "B4_14") (pintype "bidirectional"))
    )
    (net (code "62") (name "Net-(IC4-A6)") (class "Default")
      (node (ref "IC4") (pin "7") (pinfunction "A6_7") (pintype "bidirectional"))
      (node (ref "IC6") (pin "13") (pinfunction "B5_13") (pintype "bidirectional"))
    )
    (net (code "63") (name "Net-(IC4-A7)") (class "Default")
      (node (ref "IC4") (pin "8") (pinfunction "A7_8") (pintype "bidirectional"))
      (node (ref "IC6") (pin "12") (pinfunction "B6_12") (pintype "bidirectional"))
    )
    (net (code "64") (name "Net-(IC4-A8)") (class "Default")
      (node (ref "IC4") (pin "9") (pinfunction "A8_9") (pintype "bidirectional"))
      (node (ref "IC6") (pin "11") (pinfunction "B7_11") (pintype "bidirectional"))
    )
    (net (code "65") (name "Net-(IC5-A0)") (class "Default")
      (node (ref "IC5") (pin "2") (pinfunction "A0_2") (pintype "bidirectional"))
      (node (ref "RN1") (pin "8") (pinfunction "2_8") (pintype "passive"))
      (node (ref "RN5") (pin "8") (pinfunction "2_8") (pintype "passive"))
    )
    (net (code "66") (name "Net-(IC5-A1)") (class "Default")
      (node (ref "IC5") (pin "3") (pinfunction "A1_3") (pintype "bidirectional"))
      (node (ref "RN1") (pin "7") (pinfunction "2_7") (pintype "passive"))
      (node (ref "RN5") (pin "7") (pinfunction "2_7") (pintype "passive"))
    )
    (net (code "67") (name "Net-(IC5-A2)") (class "Default")
      (node (ref "IC5") (pin "4") (pinfunction "A2_4") (pintype "bidirectional"))
      (node (ref "RN1") (pin "6") (pinfunction "2_6") (pintype "passive"))
      (node (ref "RN5") (pin "6") (pinfunction "2_6") (pintype "passive"))
    )
    (net (code "68") (name "Net-(IC5-A3)") (class "Default")
      (node (ref "IC5") (pin "5") (pinfunction "A3_5") (pintype "bidirectional"))
      (node (ref "RN1") (pin "5") (pinfunction "2_5") (pintype "passive"))
      (node (ref "RN5") (pin "5") (pinfunction "2_5") (pintype "passive"))
    )
    (net (code "69") (name "Net-(IC5-A4)") (class "Default")
      (node (ref "IC5") (pin "6") (pinfunction "A4_6") (pintype "bidirectional"))
      (node (ref "RN2") (pin "8") (pinfunction "2_8") (pintype "passive"))
      (node (ref "RN6") (pin "8") (pinfunction "2_8") (pintype "passive"))
    )
    (net (code "70") (name "Net-(IC5-A5)") (class "Default")
      (node (ref "IC5") (pin "7") (pinfunction "A5_7") (pintype "bidirectional"))
      (node (ref "RN2") (pin "7") (pinfunction "2_7") (pintype "passive"))
      (node (ref "RN6") (pin "7") (pinfunction "2_7") (pintype "passive"))
    )
    (net (code "71") (name "Net-(IC5-A6)") (class "Default")
      (node (ref "IC5") (pin "8") (pinfunction "A6_8") (pintype "bidirectional"))
      (node (ref "RN2") (pin "6") (pinfunction "2_6") (pintype "passive"))
      (node (ref "RN6") (pin "6") (pinfunction "2_6") (pintype "passive"))
    )
    (net (code "72") (name "Net-(IC5-A7)") (class "Default")
      (node (ref "IC5") (pin "9") (pinfunction "A7_9") (pintype "bidirectional"))
      (node (ref "RN2") (pin "5") (pinfunction "2_5") (pintype "passive"))
      (node (ref "RN6") (pin "5") (pinfunction "2_5") (pintype "passive"))
    )
    (net (code "73") (name "Net-(IC6-A0)") (class "Default")
      (node (ref "IC6") (pin "2") (pinfunction "A0_2") (pintype "bidirectional"))
      (node (ref "RN3") (pin "8") (pinfunction "2_8") (pintype "passive"))
      (node (ref "RN7") (pin "8") (pinfunction "2_8") (pintype "passive"))
    )
    (net (code "74") (name "Net-(IC6-A1)") (class "Default")
      (node (ref "IC6") (pin "3") (pinfunction "A1_3") (pintype "bidirectional"))
      (node (ref "RN3") (pin "7") (pinfunction "2_7") (pintype "passive"))
      (node (ref "RN7") (pin "7") (pinfunction "2_7") (pintype "passive"))
    )
    (net (code "75") (name "Net-(IC6-A2)") (class "Default")
      (node (ref "IC6") (pin "4") (pinfunction "A2_4") (pintype "bidirectional"))
      (node (ref "RN3") (pin "6") (pinfunction "2_6") (pintype "passive"))
      (node (ref "RN7") (pin "6") (pinfunction "2_6") (pintype "passive"))
    )
    (net (code "76") (name "Net-(IC6-A3)") (class "Default")
      (node (ref "IC6") (pin "5") (pinfunction "A3_5") (pintype "bidirectional"))
      (node (ref "RN3") (pin "5") (pinfunction "2_5") (pintype "passive"))
      (node (ref "RN7") (pin "5") (pinfunction "2_5") (pintype "passive"))
    )
    (net (code "77") (name "Net-(IC6-A4)") (class "Default")
      (node (ref "IC6") (pin "6") (pinfunction "A4_6") (pintype "bidirectional"))
      (node (ref "RN4") (pin "8") (pinfunction "2_8") (pintype "passive"))
      (node (ref "RN8") (pin "8") (pinfunction "2_8") (pintype "passive"))
    )
    (net (code "78") (name "Net-(IC6-A5)") (class "Default")
      (node (ref "IC6") (pin "7") (pinfunction "A5_7") (pintype "bidirectional"))
      (node (ref "RN4") (pin "7") (pinfunction "2_7") (pintype "passive"))
      (node (ref "RN8") (pin "7") (pinfunction "2_7") (pintype "passive"))
    )
    (net (code "79") (name "Net-(IC6-A6)") (class "Default")
      (node (ref "IC6") (pin "8") (pinfunction "A6_8") (pintype "bidirectional"))
      (node (ref "RN4") (pin "6") (pinfunction "2_6") (pintype "passive"))
      (node (ref "RN8") (pin "6") (pinfunction "2_6") (pintype "passive"))
    )
    (net (code "80") (name "Net-(IC6-A7)") (class "Default")
      (node (ref "IC6") (pin "9") (pinfunction "A7_9") (pintype "bidirectional"))
      (node (ref "RN4") (pin "5") (pinfunction "2_5") (pintype "passive"))
      (node (ref "RN8") (pin "5") (pinfunction "2_5") (pintype "passive"))
    )
    (net (code "81") (name "Net-(J1-CC)") (class "Default")
      (node (ref "J1") (pin "A5") (pinfunction "CC_A5") (pintype "passive"))
      (node (ref "R6") (pin "2") (pinfunction "2_2") (pintype "passive"))
    )
    (net (code "82") (name "Net-(J1-VCONN)") (class "Default")
      (node (ref "J1") (pin "B5") (pinfunction "VCONN_B5") (pintype "passive"))
      (node (ref "R5") (pin "2") (pinfunction "2_2") (pintype "passive"))
    )
    (net (code "83") (name "Net-(OUT_ON-PadA)") (class "Default")
      (node (ref "OUT_ON") (pin "A") (pinfunction "A_A") (pintype "passive"))
      (node (ref "R14") (pin "2") (pinfunction "2_2") (pintype "passive"))
    )
    (net (code "84") (name "Net-(PWR-PadA)") (class "Default")
      (node (ref "PWR") (pin "A") (pinfunction "A_A") (pintype "passive"))
      (node (ref "R15") (pin "2") (pinfunction "2_2") (pintype "passive"))
    )
    (net (code "85") (name "Net-(Q1-X1)") (class "Default")
      (node (ref "C17") (pin "1") (pinfunction "1_1") (pintype "passive"))
      (node (ref "Q1") (pin "1") (pinfunction "X1_1") (pintype "bidirectional"))
      (node (ref "R12") (pin "1") (pinfunction "1_1") (pintype "passive"))
    )
    (net (code "86") (name "Net-(SW2-S)") (class "Default")
      (node (ref "R11") (pin "2") (pinfunction "2_2") (pintype "passive"))
      (node (ref "SW2") (pin "B") (pinfunction "S_B") (pintype "passive"))
      (node (ref "SW2") (pin "B'") (pinfunction "S1_B'") (pintype "passive"))
    )
    (net (code "87") (name "QSPI_SCLK") (class "Default")
      (node (ref "IC1") (pin "56") (pinfunction "QSPI_SCLK_56") (pintype "bidirectional"))
      (node (ref "IC2") (pin "6") (pinfunction "CLK_6") (pintype "bidirectional"))
    )
    (net (code "88") (name "QSPI_SD0") (class "Default")
      (node (ref "IC1") (pin "57") (pinfunction "QSPI_SD0_57") (pintype "bidirectional"))
      (node (ref "IC2") (pin "5") (pinfunction "DI/IO0_5") (pintype "bidirectional"))
    )
    (net (code "89") (name "QSPI_SD1") (class "Default")
      (node (ref "IC1") (pin "59") (pinfunction "QSPI_SD1_59") (pintype "bidirectional"))
      (node (ref "IC2") (pin "2") (pinfunction "DO/IO1_2") (pintype "bidirectional"))
    )
    (net (code "90") (name "QSPI_SD2") (class "Default")
      (node (ref "IC1") (pin "58") (pinfunction "QSPI_SD2_58") (pintype "bidirectional"))
      (node (ref "IC2") (pin "3") (pinfunction "~{WP}/IO2_3") (pintype "bidirectional"))
    )
    (net (code "91") (name "QSPI_SD3") (class "Default")
      (node (ref "IC1") (pin "55") (pinfunction "QSPI_SD3_55") (pintype "bidirectional"))
      (node (ref "IC2") (pin "7") (pinfunction "~{HOLD}/IO3_7") (pintype "bidirectional"))
    )
    (net (code "92") (name "QSPI_SS") (class "Default")
      (node (ref "IC1") (pin "60") (pinfunction "QSPI_SS_60") (pintype "bidirectional"))
      (node (ref "R3") (pin "2") (pinfunction "2_2") (pintype "passive"))
      (node (ref "R9") (pin "1") (pinfunction "1_1") (pintype "passive"))
    )
    (net (code "93") (name "RUN") (class "Default")
      (node (ref "IC1") (pin "26") (pinfunction "RUN_26") (pintype "bidirectional"))
      (node (ref "SW2") (pin "A") (pinfunction "P_A") (pintype "passive"))
      (node (ref "SW2") (pin "A'") (pinfunction "P1_A'") (pintype "passive"))
    )
    (net (code "94") (name "SPI0_CS") (class "Default")
      (node (ref "IC1") (pin "37") (pinfunction "GPIO25_37") (pintype "bidirectional"))
    )
    (net (code "95") (name "SPI0_RX") (class "Default")
      (node (ref "IC1") (pin "36") (pinfunction "GPIO24_36") (pintype "bidirectional"))
    )
    (net (code "96") (name "SPI0_SCK") (class "Default")
      (node (ref "IC1") (pin "34") (pinfunction "GPIO22_34") (pintype "bidirectional"))
    )
    (net (code "97") (name "SPI0_TX") (class "Default")
      (node (ref "IC1") (pin "35") (pinfunction "GPIO23_35") (pintype "bidirectional"))
    )
    (net (code "98") (name "SWCLK") (class "Default")
      (node (ref "DBG_SW") (pin "1") (pinfunction "1_1") (pintype "passive"))
      (node (ref "IC1") (pin "24") (pinfunction "SWCLK_24") (pintype "bidirectional"))
    )
    (net (code "99") (name "SWD") (class "Default")
      (node (ref "DBG_SW") (pin "3") (pinfunction "3_3") (pintype "passive"))
      (node (ref "IC1") (pin "25") (pinfunction "SWDIO_25") (pintype "bidirectional"))
    )
    (net (code "100") (name "UART0_RX") (class "Default")
      (node (ref "DBG_COM") (pin "4") (pinfunction "4_4") (pintype "passive"))
      (node (ref "IC1") (pin "28") (pinfunction "GPIO17_28") (pintype "bidirectional"))
    )
    (net (code "101") (name "UART0_TX") (class "Default")
      (node (ref "DBG_COM") (pin "3") (pinfunction "3_3") (pintype "passive"))
      (node (ref "IC1") (pin "27") (pinfunction "GPIO16_27") (pintype "bidirectional"))
    )
    (net (code "102") (name "UART1_RX") (class "Default")
      (node (ref "DBG_COM") (pin "2") (pinfunction "2_2") (pintype "passive"))
      (node (ref "IC1") (pin "33") (pinfunction "GPIO21_33") (pintype "bidirectional"))
    )
    (net (code "103") (name "UART1_TX") (class "Default")
      (node (ref "DBG_COM") (pin "1") (pinfunction "1_1") (pintype "passive"))
      (node (ref "IC1") (pin "32") (pinfunction "GPIO20_32") (pintype "bidirectional"))
    )
    (net (code "104") (name "USB_DM") (class "Default")
      (node (ref "ESD1") (pin "2") (pinfunction "C1_2") (pintype "bidirectional"))
      (node (ref "J1") (pin "A7") (pinfunction "DN1_A7") (pintype "passive"))
      (node (ref "J1") (pin "B7") (pinfunction "DN2_B7") (pintype "passive"))
      (node (ref "R8") (pin "2") (pinfunction "2_2") (pintype "passive"))
    )
    (net (code "105") (name "USB_DP") (class "Default")
      (node (ref "ESD1") (pin "3") (pinfunction "C2_3") (pintype "bidirectional"))
      (node (ref "J1") (pin "A6") (pinfunction "DP1_A6") (pintype "passive"))
      (node (ref "J1") (pin "B6") (pinfunction "DP2_B6") (pintype "passive"))
      (node (ref "R7") (pin "2") (pinfunction "2_2") (pintype "passive"))
    )
    (net (code "106") (name "VBUS") (class "Default")
      (node (ref "ESD1") (pin "4") (pinfunction "C3_4") (pintype "bidirectional"))
      (node (ref "J1") (pin "A4") (pinfunction "VBUS_A4") (pintype "passive"))
      (node (ref "J1") (pin "A9") (pinfunction "VBUS1_A9") (pintype "passive"))
      (node (ref "J1") (pin "B4") (pinfunction "VBUS2_B4") (pintype "passive"))
      (node (ref "J1") (pin "B9") (pinfunction "VBUS3_B9") (pintype "passive"))
      (node (ref "L1") (pin "2") (pinfunction "2_2") (pintype "passive"))
      (node (ref "R15") (pin "1") (pinfunction "1_1") (pintype "passive"))
    )
    (net (code "107") (name "VREG_LX") (class "Default")
      (node (ref "IC1") (pin "48") (pinfunction "VREG_LX_48") (pintype "power_in"))
      (node (ref "R2") (pin "1") (pinfunction "1_1") (pintype "passive"))
    )
    (net (code "108") (name "XIN") (class "Default")
      (node (ref "C16") (pin "1") (pinfunction "1_1") (pintype "passive"))
      (node (ref "IC1") (pin "21") (pinfunction "XIN_21") (pintype "input"))
      (node (ref "Q1") (pin "3") (pinfunction "X2_3") (pintype "bidirectional"))
    )
    (net (code "109") (name "XOUT") (class "Default")
      (node (ref "IC1") (pin "22") (pinfunction "XOUT_22") (pintype "output"))
      (node (ref "R12") (pin "2") (pinfunction "2_2") (pintype "passive"))
    )
    (net (code "110") (name "unconnected-(J1-SBU1-PadA8)") (class "Default")
      (node (ref "J1") (pin "A8") (pinfunction "SBU1_A8") (pintype "passive"))
    )
    (net (code "111") (name "unconnected-(J1-SBU2-PadB8)") (class "Default")
      (node (ref "J1") (pin "B8") (pinfunction "SBU2_B8") (pintype "passive"))
    )
    (net (code "112") (name "unconnected-(J1-SSRXN1-PadB10)") (class "Default")
      (node (ref "J1") (pin "B10") (pinfunction "SSRXN1_B10") (pintype "passive"))
    )
    (net (code "113") (name "unconnected-(J1-SSRXN2-PadA10)") (class "Default")
      (node (ref "J1") (pin "A10") (pinfunction "SSRXN2_A10") (pintype "passive"))
    )
    (net (code "114") (name "unconnected-(J1-SSRXP1-PadB11)") (class "Default")
      (node (ref "J1") (pin "B11") (pinfunction "SSRXP1_B11") (pintype "passive"))
    )
    (net (code "115") (name "unconnected-(J1-SSRXP2-PadA11)") (class "Default")
      (node (ref "J1") (pin "A11") (pinfunction "SSRXP2_A11") (pintype "passive"))
    )
    (net (code "116") (name "unconnected-(J1-SSTXN1-PadA3)") (class "Default")
      (node (ref "J1") (pin "A3") (pinfunction "SSTXN1_A3") (pintype "passive"))
    )
    (net (code "117") (name "unconnected-(J1-SSTXN2-PadB3)") (class "Default")
      (node (ref "J1") (pin "B3") (pinfunction "SSTXN2_B3") (pintype "passive"))
    )
    (net (code "118") (name "unconnected-(J1-SSTXP1-PadA2)") (class "Default")
      (node (ref "J1") (pin "A2") (pinfunction "SSTXP1_A2") (pintype "passive"))
    )
    (net (code "119") (name "unconnected-(J1-SSTXP2-PadB2)") (class "Default")
      (node (ref "J1") (pin "B2") (pinfunction "SSTXP2_B2") (pintype "passive"))
    )
  )
)
